# power_gateway.net
KiCad netlist of a schematic drawn in Altium Designer
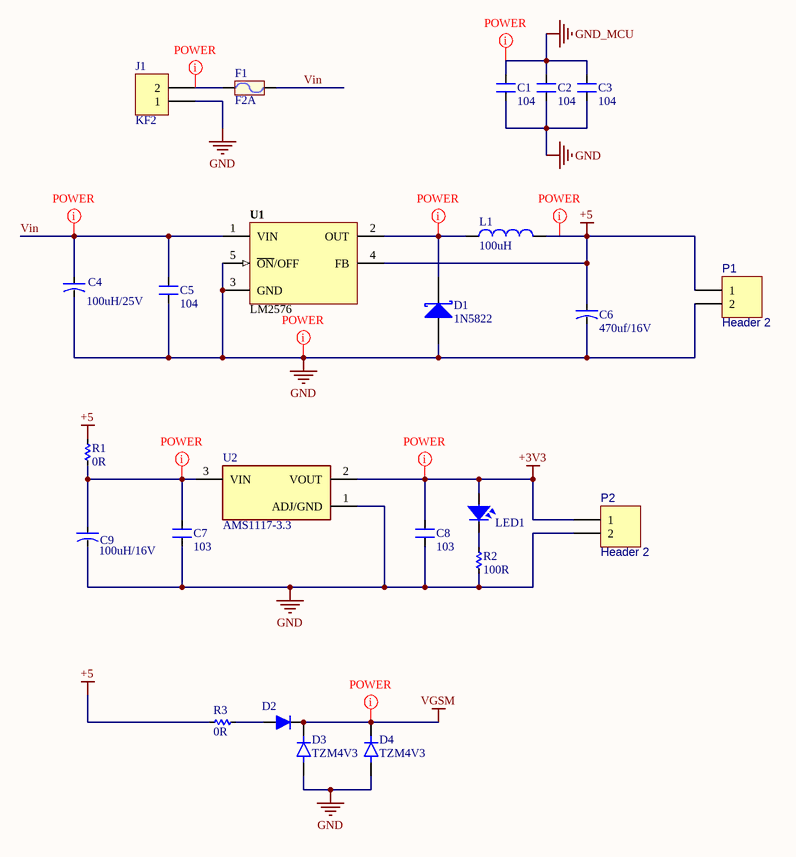
[diagram p0: power_gateway.SchDoc]

(export (version "E")
  (design (tool "Eeschema 10.0.6"))
  (components
    (comp (ref "C1")
      (value "104")
      (footprint "SM-0805")
      (description "Cap SMD")
      (libsource (lib "syhaunguyen") (part "CM"))
    )
    (comp (ref "C2")
      (value "104")
      (footprint "SM-0805")
      (description "Cap SMD")
      (libsource (lib "syhaunguyen") (part "CM"))
    )
    (comp (ref "C3")
      (value "104")
      (footprint "SM-0805")
      (description "Cap SMD")
      (libsource (lib "syhaunguyen") (part "CM"))
    )
    (comp (ref "C4")
      (value "100uH/25V")
      (footprint "CAP-ALU-SMD-6.3x7.7x2.2")
      (description "Polarized Capacitor (Axial)")
      (fields (field (name "PUBLISHER") "Altium Limited"))
      (libsource (lib "TechMT.VN_Lib_Project v2") (part "CN-ALU-SMD"))
    )
    (comp (ref "C5")
      (value "104")
      (footprint "SM-0805")
      (description "Cap SMD")
      (libsource (lib "syhaunguyen") (part "CM"))
    )
    (comp (ref "C6")
      (value "470uf/16V")
      (footprint "CAP-ALU-SMD-6.3x7.7x2.2")
      (description "Polarized Capacitor (Axial)")
      (fields (field (name "PUBLISHER") "Altium Limited"))
      (libsource (lib "TechMT.VN_Lib_Project v2") (part "CN-ALU-SMD"))
    )
    (comp (ref "C7")
      (value "103")
      (footprint "SM-0805")
      (description "Cap SMD")
      (libsource (lib "syhaunguyen") (part "CM"))
    )
    (comp (ref "C8")
      (value "103")
      (footprint "SM-0805")
      (description "Cap SMD")
      (libsource (lib "syhaunguyen") (part "CM"))
    )
    (comp (ref "C9")
      (value "100uH/16V")
      (footprint "CAP-ALU-SMD-6.3x7.7x2.2")
      (description "Polarized Capacitor (Axial)")
      (fields (field (name "PUBLISHER") "Altium Limited"))
      (libsource (lib "TechMT.VN_Lib_Project v2") (part "CN-ALU-SMD"))
    )
    (comp (ref "D1")
      (value "1N5822")
      (footprint "Diode_SS34")
      (description "Schottky diode")
      (libsource (lib "AYRIC Library") (part "1N5819"))
    )
    (comp (ref "D2")
      (value "~")
      (footprint "1N4007_SMD")
      (description "diode")
      (libsource (lib "oggy") (part "diode"))
    )
    (comp (ref "D3")
      (value "TZM4V3")
      (footprint "DIO_LL4148")
      (description "Diode Standard 100V 200mA Surface Mount SOD-80")
      (fields (field (name "MP") "LL4148") (field (name "MF") "ON Semiconductor"))
      (libsource (lib "LL4148") (part "LL4148"))
    )
    (comp (ref "D4")
      (value "TZM4V3")
      (footprint "DIO_LL4148")
      (description "Diode Standard 100V 200mA Surface Mount SOD-80")
      (fields (field (name "MP") "LL4148") (field (name "MF") "ON Semiconductor"))
      (libsource (lib "LL4148") (part "LL4148"))
    )
    (comp (ref "F1")
      (value "F2A")
      (footprint "FUSE2")
      (description "Fuse")
      (fields (field (name "DESIGNED BY") "VanDungEvn"))
      (libsource (lib "TechMT.VN_Lib_Project v2") (part "Fuse"))
    )
    (comp (ref "J1")
      (value "KF2")
      (footprint "KF2-5.08")
      (fields
        (field (name "MANUFACTURER") "Würth Elektronik eiSos GmbH")
        (field (name "PARTNO") "691103110002")
        (field (name "CREATED BY") "Karrer Zheng")
      )
      (libsource (lib "TechMT.VN_Lib_Project v2") (part "KF2"))
    )
    (comp (ref "L1")
      (value "100uH")
      (footprint "inductor_smd")
      (fields (field (name "Comment") "Inductor") (field (name "PUBLISHER") "Altium Limited"))
      (libsource (lib "AYRIC Library") (part "Inductor"))
    )
    (comp (ref "LED1")
      (value "LED")
      (footprint "LED-0805-Green")
      (libsource (lib "TechMT.VN_Lib_Project v2") (part "LED SMD"))
    )
    (comp (ref "P1")
      (value "Header 2")
      (footprint "HDR1X2")
      (description "Header, 2-Pin")
      (fields (field (name "PUBLISHER") "Altium Limited"))
      (libsource (lib "NBBLib 14-03-2012") (part "Header 2"))
    )
    (comp (ref "P2")
      (value "Header 2")
      (footprint "HDR1X2")
      (description "Header, 2-Pin")
      (fields (field (name "PUBLISHER") "Altium Limited"))
      (libsource (lib "NBBLib 14-03-2012") (part "Header 2"))
    )
    (comp (ref "R1")
      (value "0R")
      (footprint "RES-SMD-0805")
      (description "Resistor")
      (fields
        (field (name "MANUFACTURER") "Generic Components")
        (field (name "PUBLISHER") "Altium Hobart Technology Centre")
      )
      (libsource (lib "TechMT.VN_Lib_Project v2") (part "Res-SMD"))
    )
    (comp (ref "R2")
      (value "100R")
      (footprint "RES-SMD-0805")
      (description "Resistor")
      (fields
        (field (name "MANUFACTURER") "Generic Components")
        (field (name "PUBLISHER") "Altium Hobart Technology Centre")
      )
      (libsource (lib "TechMT.VN_Lib_Project v2") (part "Res-SMD"))
    )
    (comp (ref "R3")
      (value "0R")
      (footprint "RES-SMD-0805")
      (description "Resistor")
      (fields
        (field (name "MANUFACTURER") "Generic Components")
        (field (name "PUBLISHER") "Altium Hobart Technology Centre")
      )
      (libsource (lib "TechMT.VN_Lib_Project v2") (part "Res-SMD"))
    )
    (comp (ref "U1")
      (value "LM2576")
      (footprint "TO263")
      (libsource (lib "TechMT.VN_Lib_Project v2") (part "LM2576"))
    )
    (comp (ref "U2")
      (value "AMS1117-3.3")
      (footprint "SOT229P700X180-4N")
      (description "Sot223/Pkg 1-Amp 3.3-Volt Low Drop Out Voltage Regulatator")
      (fields (field (name "MF") "Advanced Monolithic Systems"))
      (libsource (lib "AMS1117-3.3") (part "AMS1117-3.3"))
    )
  )
  (nets
    (net (code "1") (name "+3V3") (class "Default")
      (node (ref "C8") (pin "1") (pinfunction "1_1") (pintype "passive"))
      (node (ref "LED1") (pin "1") (pinfunction "1_1") (pintype "passive"))
      (node (ref "P2") (pin "1") (pinfunction "1_1") (pintype "passive"))
      (node (ref "U2") (pin "2") (pinfunction "VOUT_2") (pintype "passive"))
    )
    (net (code "2") (name "+5") (class "Default")
      (node (ref "C6") (pin "1") (pinfunction "1_1") (pintype "passive"))
      (node (ref "L1") (pin "2") (pinfunction "2_2") (pintype "passive"))
      (node (ref "P1") (pin "1") (pinfunction "1_1") (pintype "passive"))
      (node (ref "R1") (pin "1") (pinfunction "1_1") (pintype "passive"))
      (node (ref "R3") (pin "1") (pinfunction "1_1") (pintype "passive"))
      (node (ref "U1") (pin "4") (pinfunction "FB_4") (pintype "passive"))
    )
    (net (code "3") (name "/Vin") (class "Default")
      (node (ref "C4") (pin "1") (pinfunction "1_1") (pintype "passive"))
      (node (ref "C5") (pin "1") (pinfunction "1_1") (pintype "passive"))
      (node (ref "F1") (pin "2") (pinfunction "2_2") (pintype "passive"))
      (node (ref "U1") (pin "1") (pinfunction "VIN_1") (pintype "power_in"))
    )
    (net (code "4") (name "GND") (class "Default")
      (node (ref "C1") (pin "1") (pinfunction "1_1") (pintype "passive"))
      (node (ref "C2") (pin "1") (pinfunction "1_1") (pintype "passive"))
      (node (ref "C3") (pin "1") (pinfunction "1_1") (pintype "passive"))
      (node (ref "C4") (pin "2") (pinfunction "2_2") (pintype "passive"))
      (node (ref "C5") (pin "2") (pinfunction "2_2") (pintype "passive"))
      (node (ref "C6") (pin "2") (pinfunction "2_2") (pintype "passive"))
      (node (ref "C7") (pin "2") (pinfunction "2_2") (pintype "passive"))
      (node (ref "C8") (pin "2") (pinfunction "2_2") (pintype "passive"))
      (node (ref "C9") (pin "2") (pinfunction "2_2") (pintype "passive"))
      (node (ref "D1") (pin "1") (pinfunction "A_1") (pintype "passive"))
      (node (ref "D3") (pin "A") (pinfunction "A_A") (pintype "passive"))
      (node (ref "D4") (pin "A") (pinfunction "A_A") (pintype "passive"))
      (node (ref "J1") (pin "1") (pinfunction "1_1") (pintype "passive"))
      (node (ref "P1") (pin "2") (pinfunction "2_2") (pintype "passive"))
      (node (ref "P2") (pin "2") (pinfunction "2_2") (pintype "passive"))
      (node (ref "R2") (pin "2") (pinfunction "2_2") (pintype "passive"))
      (node (ref "U1") (pin "3") (pinfunction "GND_3") (pintype "power_in"))
      (node (ref "U1") (pin "5") (pinfunction "~{ON}/OFF_5") (pintype "input"))
      (node (ref "U2") (pin "1") (pinfunction "ADJ/GND_1") (pintype "power_in"))
    )
    (net (code "5") (name "GND_MCU") (class "Default")
      (node (ref "C1") (pin "2") (pinfunction "2_2") (pintype "passive"))
      (node (ref "C2") (pin "2") (pinfunction "2_2") (pintype "passive"))
      (node (ref "C3") (pin "2") (pinfunction "2_2") (pintype "passive"))
    )
    (net (code "6") (name "Net-(D1-K)") (class "Default")
      (node (ref "D1") (pin "2") (pinfunction "K_2") (pintype "passive"))
      (node (ref "L1") (pin "1") (pinfunction "1_1") (pintype "passive"))
      (node (ref "U1") (pin "2") (pinfunction "OUT_2") (pintype "power_in"))
    )
    (net (code "7") (name "Net-(D2-Pad1)") (class "Default")
      (node (ref "D2") (pin "1") (pinfunction "1_1") (pintype "passive"))
      (node (ref "R3") (pin "2") (pinfunction "2_2") (pintype "passive"))
    )
    (net (code "8") (name "Net-(F1-Pad1)") (class "Default")
      (node (ref "F1") (pin "1") (pinfunction "1_1") (pintype "passive"))
      (node (ref "J1") (pin "2") (pinfunction "2_2") (pintype "passive"))
    )
    (net (code "9") (name "Net-(LED1-Pad2)") (class "Default")
      (node (ref "LED1") (pin "2") (pinfunction "2_2") (pintype "passive"))
      (node (ref "R2") (pin "1") (pinfunction "1_1") (pintype "passive"))
    )
    (net (code "10") (name "Net-(U2-VIN)") (class "Default")
      (node (ref "C7") (pin "1") (pinfunction "1_1") (pintype "passive"))
      (node (ref "C9") (pin "1") (pinfunction "1_1") (pintype "passive"))
      (node (ref "R1") (pin "2") (pinfunction "2_2") (pintype "passive"))
      (node (ref "U2") (pin "3") (pinfunction "VIN_3") (pintype "passive"))
    )
    (net (code "11") (name "VGSM") (class "Default")
      (node (ref "D2") (pin "2") (pinfunction "2_2") (pintype "passive"))
      (node (ref "D3") (pin "C") (pinfunction "C_C") (pintype "passive"))
      (node (ref "D4") (pin "C") (pinfunction "C_C") (pintype "passive"))
    )
  )
)
